# PCB_111000_CC.net
KiCad netlist of a schematic drawn in EAGLE
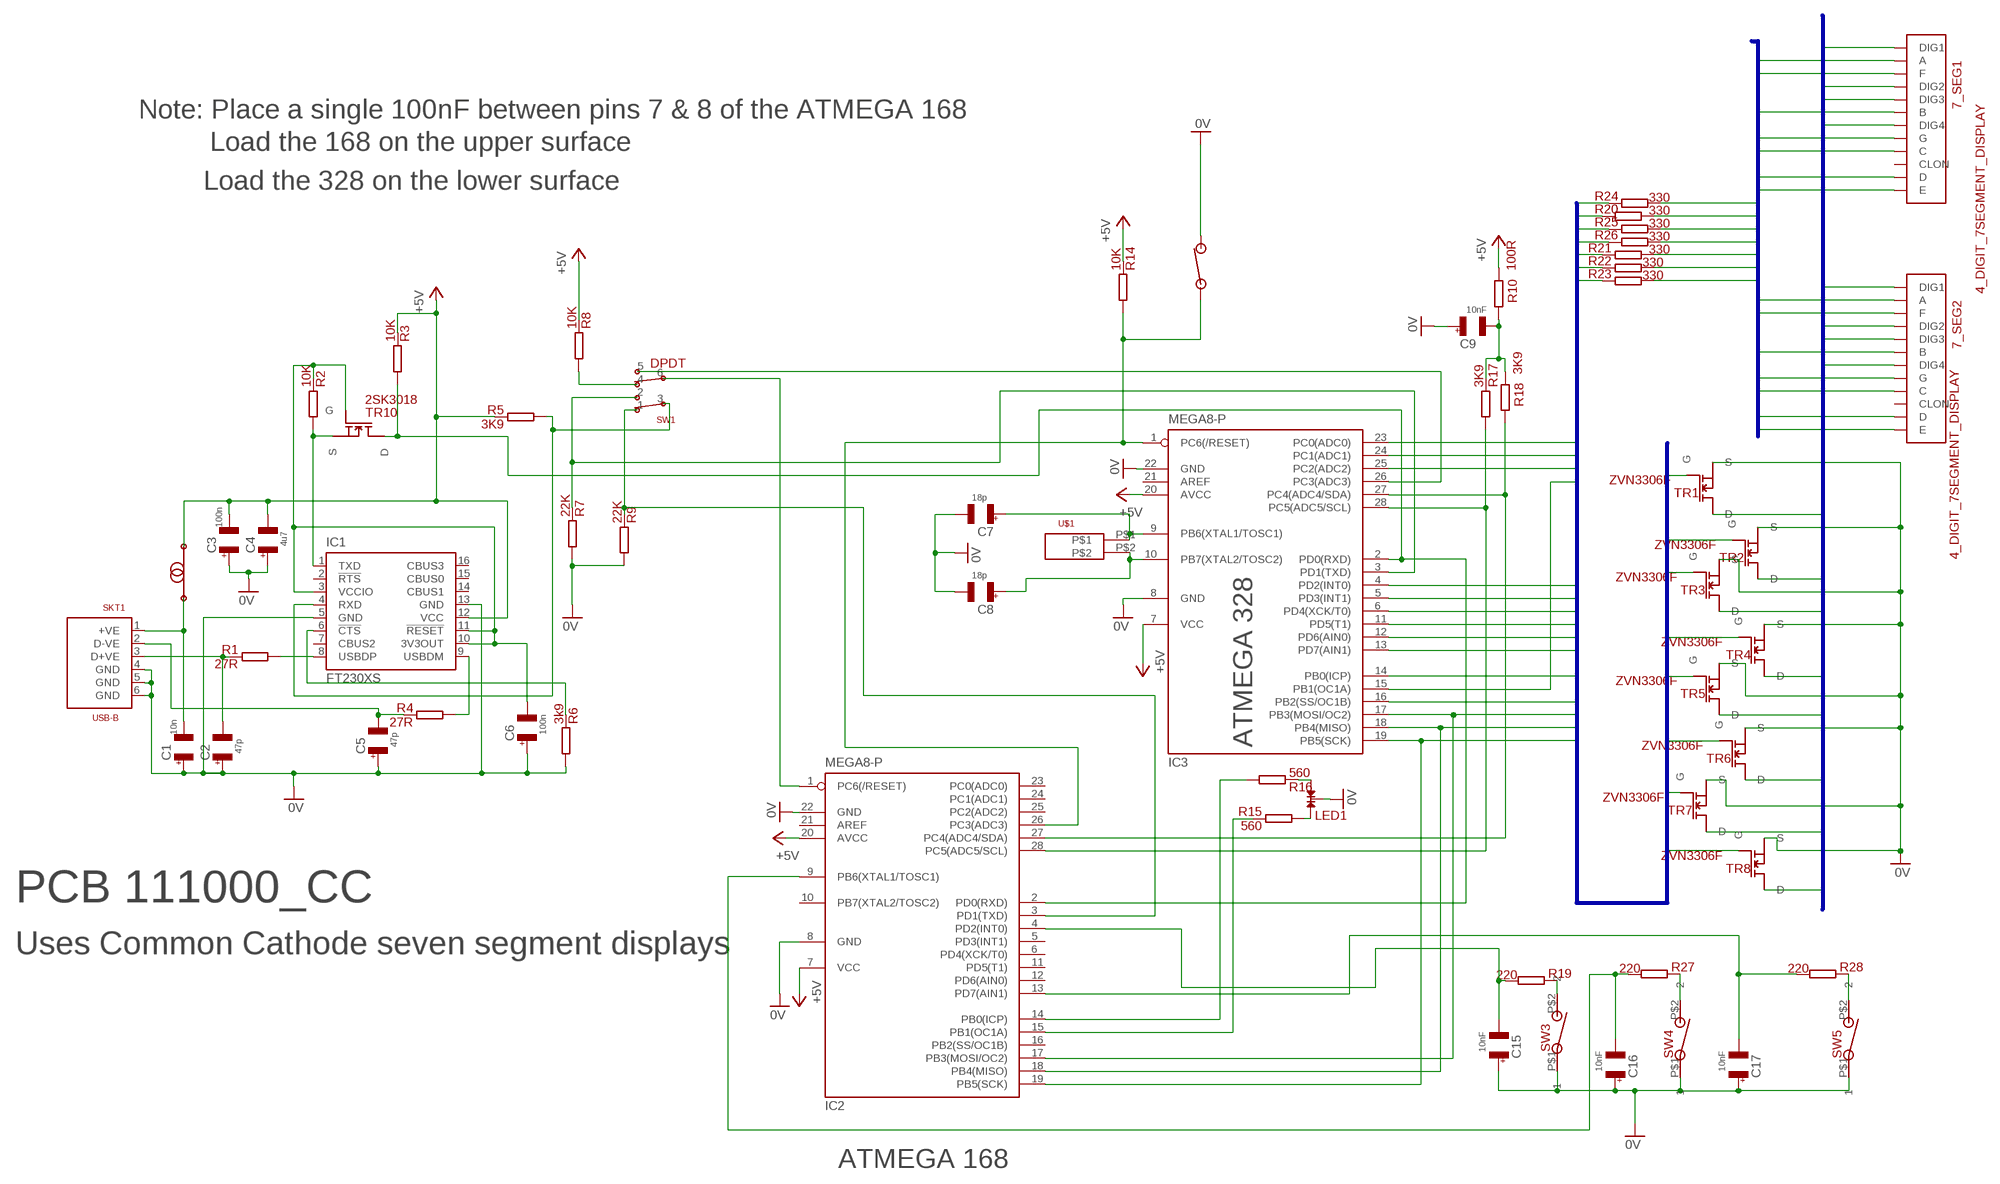
[diagram p0: schematic, sheet 1]

(export (version "E")
  (design (tool "Eeschema 10.0.6"))
  (components
    (comp (ref "7_SEG1")
      (value "4_DIGIT_7SEGMENT_DISPLAY")
      (footprint "eagle-import:4_DIGIT_7SEGMENT_DISPLAY")
      (libsource (lib "eagle-import") (part "4_DIGIT_7SEGMENT_DISPLAY"))
    )
    (comp (ref "7_SEG2")
      (value "4_DIGIT_7SEGMENT_DISPLAY")
      (footprint "eagle-import:4_DIGIT_7SEGMENT_DISPLAY")
      (libsource (lib "eagle-import") (part "4_DIGIT_7SEGMENT_DISPLAY"))
    )
    (comp (ref "C1")
      (value "10n")
      (footprint "eagle-import:1206")
      (libsource (lib "eagle-import") (part "1206C"))
    )
    (comp (ref "C2")
      (value "47p")
      (footprint "eagle-import:1206")
      (libsource (lib "eagle-import") (part "1206C"))
    )
    (comp (ref "C3")
      (value "100n")
      (footprint "eagle-import:1206")
      (libsource (lib "eagle-import") (part "1206C"))
    )
    (comp (ref "C4")
      (value "4u7")
      (footprint "eagle-import:1206")
      (libsource (lib "eagle-import") (part "1206C"))
    )
    (comp (ref "C5")
      (value "47p")
      (footprint "eagle-import:1206")
      (libsource (lib "eagle-import") (part "1206C"))
    )
    (comp (ref "C6")
      (value "100n")
      (footprint "eagle-import:1206")
      (libsource (lib "eagle-import") (part "1206C"))
    )
    (comp (ref "C7")
      (value "18p")
      (footprint "eagle-import:0805")
      (libsource (lib "eagle-import") (part "0805C"))
    )
    (comp (ref "C8")
      (value "18p")
      (footprint "eagle-import:0805")
      (libsource (lib "eagle-import") (part "0805C"))
    )
    (comp (ref "C9")
      (value "10nF")
      (footprint "eagle-import:1206")
      (libsource (lib "eagle-import") (part "1206C"))
    )
    (comp (ref "C15")
      (value "10nF")
      (footprint "eagle-import:1206")
      (libsource (lib "eagle-import") (part "1206C"))
    )
    (comp (ref "C16")
      (value "10nF")
      (footprint "eagle-import:1206")
      (libsource (lib "eagle-import") (part "1206C"))
    )
    (comp (ref "C17")
      (value "10nF")
      (footprint "eagle-import:1206")
      (libsource (lib "eagle-import") (part "1206C"))
    )
    (comp (ref "IC1")
      (value "FT230XS")
      (footprint "eagle-import:SSOP16")
      (libsource (lib "eagle-import") (part "FT230XS"))
    )
    (comp (ref "IC2")
      (value "MEGA8-P")
      (footprint "eagle-import:DIL28-3")
      (libsource (lib "eagle-import") (part "MEGA8-P"))
    )
    (comp (ref "IC3")
      (value "MEGA8-P")
      (footprint "eagle-import:DIL28-3")
      (libsource (lib "eagle-import") (part "MEGA8-P"))
    )
    (comp (ref "L1")
      (value "CHOKE")
      (footprint "eagle-import:1206")
      (libsource (lib "eagle-import") (part "CHOKE"))
    )
    (comp (ref "LED1")
      (value "LED")
      (footprint "eagle-import:CA_DUAL_LED")
      (libsource (lib "eagle-import") (part "LED"))
    )
    (comp (ref "R1")
      (value "27R")
      (footprint "eagle-import:1206")
      (libsource (lib "eagle-import") (part "1206R"))
    )
    (comp (ref "R2")
      (value "10K")
      (footprint "eagle-import:1206")
      (libsource (lib "eagle-import") (part "1206R"))
    )
    (comp (ref "R3")
      (value "10K")
      (footprint "eagle-import:1206")
      (libsource (lib "eagle-import") (part "1206R"))
    )
    (comp (ref "R4")
      (value "27R")
      (footprint "eagle-import:1206")
      (libsource (lib "eagle-import") (part "1206R"))
    )
    (comp (ref "R5")
      (value "3K9")
      (footprint "eagle-import:1206")
      (libsource (lib "eagle-import") (part "1206R"))
    )
    (comp (ref "R6")
      (value "3k9")
      (footprint "eagle-import:1206")
      (libsource (lib "eagle-import") (part "1206R"))
    )
    (comp (ref "R7")
      (value "22K")
      (footprint "eagle-import:1206")
      (libsource (lib "eagle-import") (part "1206R"))
    )
    (comp (ref "R8")
      (value "10K")
      (footprint "eagle-import:1206")
      (libsource (lib "eagle-import") (part "1206R"))
    )
    (comp (ref "R9")
      (value "22K")
      (footprint "eagle-import:1206")
      (libsource (lib "eagle-import") (part "1206R"))
    )
    (comp (ref "R10")
      (value "100R")
      (footprint "eagle-import:1206")
      (libsource (lib "eagle-import") (part "1206R"))
    )
    (comp (ref "R14")
      (value "10K")
      (footprint "eagle-import:1206")
      (libsource (lib "eagle-import") (part "1206R"))
    )
    (comp (ref "R15")
      (value "560")
      (footprint "eagle-import:1206")
      (libsource (lib "eagle-import") (part "1206R"))
    )
    (comp (ref "R16")
      (value "560")
      (footprint "eagle-import:1206")
      (libsource (lib "eagle-import") (part "1206R"))
    )
    (comp (ref "R17")
      (value "3K9")
      (footprint "eagle-import:1206")
      (libsource (lib "eagle-import") (part "1206R"))
    )
    (comp (ref "R18")
      (value "3K9")
      (footprint "eagle-import:1206")
      (libsource (lib "eagle-import") (part "1206R"))
    )
    (comp (ref "R19")
      (value "220")
      (footprint "eagle-import:1206")
      (libsource (lib "eagle-import") (part "1206R"))
    )
    (comp (ref "R20")
      (value "330")
      (footprint "eagle-import:1206")
      (libsource (lib "eagle-import") (part "1206R"))
    )
    (comp (ref "R21")
      (value "330")
      (footprint "eagle-import:1206")
      (libsource (lib "eagle-import") (part "1206R"))
    )
    (comp (ref "R22")
      (value "330")
      (footprint "eagle-import:1206")
      (libsource (lib "eagle-import") (part "1206R"))
    )
    (comp (ref "R23")
      (value "330")
      (footprint "eagle-import:1206")
      (libsource (lib "eagle-import") (part "1206R"))
    )
    (comp (ref "R24")
      (value "330")
      (footprint "eagle-import:1206")
      (libsource (lib "eagle-import") (part "1206R"))
    )
    (comp (ref "R25")
      (value "330")
      (footprint "eagle-import:1206")
      (libsource (lib "eagle-import") (part "1206R"))
    )
    (comp (ref "R26")
      (value "330")
      (footprint "eagle-import:1206")
      (libsource (lib "eagle-import") (part "1206R"))
    )
    (comp (ref "R27")
      (value "220")
      (footprint "eagle-import:1206")
      (libsource (lib "eagle-import") (part "1206R"))
    )
    (comp (ref "R28")
      (value "220")
      (footprint "eagle-import:1206")
      (libsource (lib "eagle-import") (part "1206R"))
    )
    (comp (ref "SKT1")
      (value "USB-B")
      (footprint "eagle-import:USB-B")
      (libsource (lib "eagle-import") (part "USB-B"))
    )
    (comp (ref "SW1")
      (value "DPDT")
      (footprint "eagle-import:DPDT_SWITCH")
      (libsource (lib "eagle-import") (part "DPDT"))
    )
    (comp (ref "SW2")
      (value "NO_SW")
      (footprint "eagle-import:SM_NO_PUSH_BUTTON")
      (libsource (lib "eagle-import") (part "NO_SW"))
    )
    (comp (ref "SW3")
      (value "NO_PB_1")
      (footprint "eagle-import:RE51-0711")
      (libsource (lib "eagle-import") (part "NO_PB_1"))
    )
    (comp (ref "SW4")
      (value "NO_PB_1")
      (footprint "eagle-import:RE51-0711")
      (libsource (lib "eagle-import") (part "NO_PB_1"))
    )
    (comp (ref "SW5")
      (value "NO_PB_1")
      (footprint "eagle-import:RE51-0711")
      (libsource (lib "eagle-import") (part "NO_PB_1"))
    )
    (comp (ref "TR1")
      (value "ZVN3306F")
      (footprint "eagle-import:SOT23")
      (libsource (lib "eagle-import") (part "ZVN3306F"))
    )
    (comp (ref "TR2")
      (value "ZVN3306F")
      (footprint "eagle-import:SOT23")
      (libsource (lib "eagle-import") (part "ZVN3306F"))
    )
    (comp (ref "TR3")
      (value "ZVN3306F")
      (footprint "eagle-import:SOT23")
      (libsource (lib "eagle-import") (part "ZVN3306F"))
    )
    (comp (ref "TR4")
      (value "ZVN3306F")
      (footprint "eagle-import:SOT23")
      (libsource (lib "eagle-import") (part "ZVN3306F"))
    )
    (comp (ref "TR5")
      (value "ZVN3306F")
      (footprint "eagle-import:SOT23")
      (libsource (lib "eagle-import") (part "ZVN3306F"))
    )
    (comp (ref "TR6")
      (value "ZVN3306F")
      (footprint "eagle-import:SOT23")
      (libsource (lib "eagle-import") (part "ZVN3306F"))
    )
    (comp (ref "TR7")
      (value "ZVN3306F")
      (footprint "eagle-import:SOT23")
      (libsource (lib "eagle-import") (part "ZVN3306F"))
    )
    (comp (ref "TR8")
      (value "ZVN3306F")
      (footprint "eagle-import:SOT23")
      (libsource (lib "eagle-import") (part "ZVN3306F"))
    )
    (comp (ref "TR10")
      (value "2SK3018")
      (footprint "eagle-import:2SK3018")
      (libsource (lib "eagle-import") (part "2SK3018"))
    )
    (comp (ref "U$1")
      (value "XTAL")
      (footprint "eagle-import:XTAL_VIAS")
      (libsource (lib "eagle-import") (part "XTAL"))
    )
  )
  (nets
    (net (code "1") (name "+5V") (class "Default")
      (node (ref "C3") (pin "P$2") (pinfunction "2_P$2") (pintype "bidirectional"))
      (node (ref "C4") (pin "P$2") (pinfunction "2_P$2") (pintype "bidirectional"))
      (node (ref "IC1") (pin "12") (pinfunction "VCC_12") (pintype "power_in"))
      (node (ref "IC2") (pin "20") (pinfunction "AVCC_20") (pintype "power_in"))
      (node (ref "IC2") (pin "7") (pinfunction "VCC_7") (pintype "power_in"))
      (node (ref "IC3") (pin "20") (pinfunction "AVCC_20") (pintype "power_in"))
      (node (ref "IC3") (pin "7") (pinfunction "VCC_7") (pintype "power_in"))
      (node (ref "L1") (pin "P$2") (pinfunction "2_P$2") (pintype "bidirectional"))
      (node (ref "R10") (pin "P$2") (pinfunction "P$2_P$2") (pintype "bidirectional"))
      (node (ref "R14") (pin "P$2") (pinfunction "P$2_P$2") (pintype "bidirectional"))
      (node (ref "R3") (pin "P$2") (pinfunction "P$2_P$2") (pintype "bidirectional"))
      (node (ref "R5") (pin "P$2") (pinfunction "P$2_P$2") (pintype "bidirectional"))
      (node (ref "R8") (pin "P$2") (pinfunction "P$2_P$2") (pintype "bidirectional"))
    )
    (net (code "2") (name "/DIGIT0") (class "Default")
      (node (ref "7_SEG1") (pin "P$12") (pinfunction "DIG1_P$12") (pintype "bidirectional"))
      (node (ref "TR5") (pin "3") (pinfunction "D_3") (pintype "bidirectional"))
    )
    (net (code "3") (name "/DIGIT1") (class "Default")
      (node (ref "7_SEG1") (pin "P$9") (pinfunction "DIG2_P$9") (pintype "bidirectional"))
      (node (ref "TR6") (pin "3") (pinfunction "D_3") (pintype "bidirectional"))
    )
    (net (code "4") (name "/DIGIT2") (class "Default")
      (node (ref "7_SEG1") (pin "P$8") (pinfunction "DIG3_P$8") (pintype "bidirectional"))
      (node (ref "TR7") (pin "3") (pinfunction "D_3") (pintype "bidirectional"))
    )
    (net (code "5") (name "/DIGIT3") (class "Default")
      (node (ref "7_SEG1") (pin "P$6") (pinfunction "DIG4_P$6") (pintype "bidirectional"))
      (node (ref "TR8") (pin "3") (pinfunction "D_3") (pintype "bidirectional"))
    )
    (net (code "6") (name "/DIGIT4") (class "Default")
      (node (ref "7_SEG2") (pin "P$12") (pinfunction "DIG1_P$12") (pintype "bidirectional"))
      (node (ref "TR1") (pin "3") (pinfunction "D_3") (pintype "bidirectional"))
    )
    (net (code "7") (name "/DIGIT5") (class "Default")
      (node (ref "7_SEG2") (pin "P$9") (pinfunction "DIG2_P$9") (pintype "bidirectional"))
      (node (ref "TR2") (pin "3") (pinfunction "D_3") (pintype "bidirectional"))
    )
    (net (code "8") (name "/DIGIT6") (class "Default")
      (node (ref "7_SEG2") (pin "P$8") (pinfunction "DIG3_P$8") (pintype "bidirectional"))
      (node (ref "TR3") (pin "3") (pinfunction "D_3") (pintype "bidirectional"))
    )
    (net (code "9") (name "/DIGIT7") (class "Default")
      (node (ref "7_SEG2") (pin "P$6") (pinfunction "DIG4_P$6") (pintype "bidirectional"))
      (node (ref "TR4") (pin "3") (pinfunction "D_3") (pintype "bidirectional"))
    )
    (net (code "10") (name "/DISPLAY_DRIVER0") (class "Default")
      (node (ref "IC3") (pin "15") (pinfunction "PB1(OC1A)_15") (pintype "bidirectional"))
      (node (ref "R24") (pin "P$2") (pinfunction "P$2_P$2") (pintype "bidirectional"))
    )
    (net (code "11") (name "/DISPLAY_DRIVER1") (class "Default")
      (node (ref "IC3") (pin "4") (pinfunction "PD2(INT0)_4") (pintype "bidirectional"))
      (node (ref "R20") (pin "P$2") (pinfunction "P$2_P$2") (pintype "bidirectional"))
    )
    (net (code "12") (name "/DISPLAY_DRIVER2") (class "Default")
      (node (ref "IC3") (pin "5") (pinfunction "PD3(INT1)_5") (pintype "bidirectional"))
      (node (ref "R25") (pin "P$2") (pinfunction "P$2_P$2") (pintype "bidirectional"))
    )
    (net (code "13") (name "/DISPLAY_DRIVER3") (class "Default")
      (node (ref "IC3") (pin "6") (pinfunction "PD4(XCK/T0)_6") (pintype "bidirectional"))
      (node (ref "R26") (pin "P$2") (pinfunction "P$2_P$2") (pintype "bidirectional"))
    )
    (net (code "14") (name "/DISPLAY_DRIVER4") (class "Default")
      (node (ref "IC3") (pin "11") (pinfunction "PD5(T1)_11") (pintype "bidirectional"))
      (node (ref "R21") (pin "P$2") (pinfunction "P$2_P$2") (pintype "bidirectional"))
    )
    (net (code "15") (name "/DISPLAY_DRIVER5") (class "Default")
      (node (ref "IC3") (pin "12") (pinfunction "PD6(AIN0)_12") (pintype "bidirectional"))
      (node (ref "R22") (pin "P$2") (pinfunction "P$2_P$2") (pintype "bidirectional"))
    )
    (net (code "16") (name "/DISPLAY_DRIVER6") (class "Default")
      (node (ref "IC3") (pin "13") (pinfunction "PD7(AIN1)_13") (pintype "bidirectional"))
      (node (ref "R23") (pin "P$2") (pinfunction "P$2_P$2") (pintype "bidirectional"))
    )
    (net (code "17") (name "/DISPLAY_DRIVER8") (class "Default")
      (node (ref "IC3") (pin "14") (pinfunction "PB0(ICP)_14") (pintype "bidirectional"))
      (node (ref "TR1") (pin "1") (pinfunction "G_1") (pintype "bidirectional"))
    )
    (net (code "18") (name "/DISPLAY_DRIVER9") (class "Default")
      (node (ref "IC3") (pin "16") (pinfunction "PB2(SS/OC1B)_16") (pintype "bidirectional"))
      (node (ref "TR2") (pin "1") (pinfunction "G_1") (pintype "bidirectional"))
    )
    (net (code "19") (name "/DISPLAY_DRIVER10") (class "Default")
      (node (ref "IC2") (pin "17") (pinfunction "PB3(MOSI/OC2)_17") (pintype "bidirectional"))
      (node (ref "IC3") (pin "17") (pinfunction "PB3(MOSI/OC2)_17") (pintype "bidirectional"))
      (node (ref "TR3") (pin "1") (pinfunction "G_1") (pintype "bidirectional"))
    )
    (net (code "20") (name "/DISPLAY_DRIVER11") (class "Default")
      (node (ref "IC2") (pin "18") (pinfunction "PB4(MISO)_18") (pintype "bidirectional"))
      (node (ref "IC3") (pin "18") (pinfunction "PB4(MISO)_18") (pintype "bidirectional"))
      (node (ref "TR4") (pin "1") (pinfunction "G_1") (pintype "bidirectional"))
    )
    (net (code "21") (name "/DISPLAY_DRIVER12") (class "Default")
      (node (ref "IC2") (pin "19") (pinfunction "PB5(SCK)_19") (pintype "bidirectional"))
      (node (ref "IC3") (pin "19") (pinfunction "PB5(SCK)_19") (pintype "bidirectional"))
      (node (ref "TR5") (pin "1") (pinfunction "G_1") (pintype "bidirectional"))
    )
    (net (code "22") (name "/DISPLAY_DRIVER13") (class "Default")
      (node (ref "IC3") (pin "23") (pinfunction "PC0(ADC0)_23") (pintype "bidirectional"))
      (node (ref "TR6") (pin "1") (pinfunction "G_1") (pintype "bidirectional"))
    )
    (net (code "23") (name "/DISPLAY_DRIVER14") (class "Default")
      (node (ref "IC3") (pin "24") (pinfunction "PC1(ADC1)_24") (pintype "bidirectional"))
      (node (ref "TR7") (pin "1") (pinfunction "G_1") (pintype "bidirectional"))
    )
    (net (code "24") (name "/DISPLAY_DRIVER15") (class "Default")
      (node (ref "IC3") (pin "25") (pinfunction "PC2(ADC2)_25") (pintype "bidirectional"))
      (node (ref "TR8") (pin "1") (pinfunction "G_1") (pintype "bidirectional"))
    )
    (net (code "25") (name "/SEVEN_SEG0") (class "Default")
      (node (ref "7_SEG1") (pin "P$11") (pinfunction "A_P$11") (pintype "bidirectional"))
      (node (ref "7_SEG2") (pin "P$11") (pinfunction "A_P$11") (pintype "bidirectional"))
      (node (ref "R24") (pin "P$1") (pinfunction "P$1_P$1") (pintype "bidirectional"))
    )
    (net (code "26") (name "/SEVEN_SEG1") (class "Default")
      (node (ref "7_SEG1") (pin "P$7") (pinfunction "B_P$7") (pintype "bidirectional"))
      (node (ref "7_SEG2") (pin "P$7") (pinfunction "B_P$7") (pintype "bidirectional"))
      (node (ref "R20") (pin "P$1") (pinfunction "P$1_P$1") (pintype "bidirectional"))
    )
    (net (code "27") (name "/SEVEN_SEG2") (class "Default")
      (node (ref "7_SEG1") (pin "P$4") (pinfunction "C_P$4") (pintype "bidirectional"))
      (node (ref "7_SEG2") (pin "P$4") (pinfunction "C_P$4") (pintype "bidirectional"))
      (node (ref "R25") (pin "P$1") (pinfunction "P$1_P$1") (pintype "bidirectional"))
    )
    (net (code "28") (name "/SEVEN_SEG3") (class "Default")
      (node (ref "7_SEG1") (pin "P$2") (pinfunction "D_P$2") (pintype "bidirectional"))
      (node (ref "7_SEG2") (pin "P$2") (pinfunction "D_P$2") (pintype "bidirectional"))
      (node (ref "R26") (pin "P$1") (pinfunction "P$1_P$1") (pintype "bidirectional"))
    )
    (net (code "29") (name "/SEVEN_SEG4") (class "Default")
      (node (ref "7_SEG1") (pin "P$1") (pinfunction "E_P$1") (pintype "bidirectional"))
      (node (ref "7_SEG2") (pin "P$1") (pinfunction "E_P$1") (pintype "bidirectional"))
      (node (ref "R21") (pin "P$1") (pinfunction "P$1_P$1") (pintype "bidirectional"))
    )
    (net (code "30") (name "/SEVEN_SEG5") (class "Default")
      (node (ref "7_SEG1") (pin "P$10") (pinfunction "F_P$10") (pintype "bidirectional"))
      (node (ref "7_SEG2") (pin "P$10") (pinfunction "F_P$10") (pintype "bidirectional"))
      (node (ref "R22") (pin "P$1") (pinfunction "P$1_P$1") (pintype "bidirectional"))
    )
    (net (code "31") (name "/SEVEN_SEG6") (class "Default")
      (node (ref "7_SEG1") (pin "P$5") (pinfunction "G_P$5") (pintype "bidirectional"))
      (node (ref "7_SEG2") (pin "P$5") (pinfunction "G_P$5") (pintype "bidirectional"))
      (node (ref "R23") (pin "P$1") (pinfunction "P$1_P$1") (pintype "bidirectional"))
    )
    (net (code "32") (name "0V") (class "Default")
      (node (ref "C1") (pin "P$1") (pinfunction "1_P$1") (pintype "bidirectional"))
      (node (ref "C15") (pin "P$1") (pinfunction "1_P$1") (pintype "bidirectional"))
      (node (ref "C16") (pin "P$1") (pinfunction "1_P$1") (pintype "bidirectional"))
      (node (ref "C17") (pin "P$1") (pinfunction "1_P$1") (pintype "bidirectional"))
      (node (ref "C2") (pin "P$1") (pinfunction "1_P$1") (pintype "bidirectional"))
      (node (ref "C3") (pin "P$1") (pinfunction "1_P$1") (pintype "bidirectional"))
      (node (ref "C4") (pin "P$1") (pinfunction "1_P$1") (pintype "bidirectional"))
      (node (ref "C5") (pin "P$1") (pinfunction "1_P$1") (pintype "bidirectional"))
      (node (ref "C6") (pin "P$1") (pinfunction "1_P$1") (pintype "bidirectional"))
      (node (ref "C7") (pin "2") (pinfunction "2_2") (pintype "bidirectional"))
      (node (ref "C8") (pin "2") (pinfunction "2_2") (pintype "bidirectional"))
      (node (ref "C9") (pin "P$1") (pinfunction "1_P$1") (pintype "bidirectional"))
      (node (ref "IC1") (pin "13") (pinfunction "GND_13") (pintype "power_in"))
      (node (ref "IC1") (pin "5") (pinfunction "GND_5") (pintype "power_in"))
      (node (ref "IC2") (pin "22") (pinfunction "GND_22") (pintype "power_in"))
      (node (ref "IC2") (pin "8") (pinfunction "GND_8") (pintype "power_in"))
      (node (ref "IC3") (pin "22") (pinfunction "GND_22") (pintype "power_in"))
      (node (ref "IC3") (pin "8") (pinfunction "GND_8") (pintype "power_in"))
      (node (ref "LED1") (pin "2") (pinfunction "2_2") (pintype "bidirectional"))
      (node (ref "R6") (pin "P$1") (pinfunction "P$1_P$1") (pintype "bidirectional"))
      (node (ref "R7") (pin "P$1") (pinfunction "P$1_P$1") (pintype "bidirectional"))
      (node (ref "R9") (pin "P$1") (pinfunction "P$1_P$1") (pintype "bidirectional"))
      (node (ref "SKT1") (pin "4") (pinfunction "GND_4") (pintype "bidirectional"))
      (node (ref "SKT1") (pin "5") (pinfunction "GND_5") (pintype "bidirectional"))
      (node (ref "SKT1") (pin "6") (pinfunction "GND_6") (pintype "bidirectional"))
      (node (ref "SW2") (pin "P$2") (pinfunction "2_P$2") (pintype "bidirectional"))
      (node (ref "SW3") (pin "P$1") (pinfunction "1_P$1") (pintype "bidirectional"))
      (node (ref "SW4") (pin "P$1") (pinfunction "1_P$1") (pintype "bidirectional"))
      (node (ref "SW5") (pin "P$1") (pinfunction "1_P$1") (pintype "bidirectional"))
      (node (ref "TR1") (pin "2") (pinfunction "S_2") (pintype "bidirectional"))
      (node (ref "TR2") (pin "2") (pinfunction "S_2") (pintype "bidirectional"))
      (node (ref "TR3") (pin "2") (pinfunction "S_2") (pintype "bidirectional"))
      (node (ref "TR4") (pin "2") (pinfunction "S_2") (pintype "bidirectional"))
      (node (ref "TR5") (pin "2") (pinfunction "S_2") (pintype "bidirectional"))
      (node (ref "TR6") (pin "2") (pinfunction "S_2") (pintype "bidirectional"))
      (node (ref "TR7") (pin "2") (pinfunction "S_2") (pintype "bidirectional"))
      (node (ref "TR8") (pin "2") (pinfunction "S_2") (pintype "bidirectional"))
    )
    (net (code "33") (name "Net-(C1-2)") (class "Default")
      (node (ref "C1") (pin "P$2") (pinfunction "2_P$2") (pintype "bidirectional"))
      (node (ref "L1") (pin "P$1") (pinfunction "1_P$1") (pintype "bidirectional"))
      (node (ref "SKT1") (pin "1") (pinfunction "+VE_1") (pintype "bidirectional"))
    )
    (net (code "34") (name "Net-(C2-2)") (class "Default")
      (node (ref "C2") (pin "P$2") (pinfunction "2_P$2") (pintype "bidirectional"))
      (node (ref "R1") (pin "P$2") (pinfunction "P$2_P$2") (pintype "bidirectional"))
      (node (ref "SKT1") (pin "3") (pinfunction "D+VE_3") (pintype "bidirectional"))
    )
    (net (code "35") (name "Net-(C5-2)") (class "Default")
      (node (ref "C5") (pin "P$2") (pinfunction "2_P$2") (pintype "bidirectional"))
      (node (ref "R4") (pin "P$2") (pinfunction "P$2_P$2") (pintype "bidirectional"))
      (node (ref "SKT1") (pin "2") (pinfunction "D-VE_2") (pintype "bidirectional"))
    )
    (net (code "36") (name "Net-(C6-2)") (class "Default")
      (node (ref "C6") (pin "P$2") (pinfunction "2_P$2") (pintype "bidirectional"))
      (node (ref "IC1") (pin "10") (pinfunction "3V3OUT_10") (pintype "output"))
      (node (ref "IC1") (pin "11") (pinfunction "~{RESET}_11") (pintype "input"))
      (node (ref "IC1") (pin "3") (pinfunction "VCCIO_3") (pintype "power_in"))
      (node (ref "R2") (pin "P$2") (pinfunction "P$2_P$2") (pintype "bidirectional"))
      (node (ref "TR10") (pin "2") (pinfunction "G_2") (pintype "bidirectional"))
    )
    (net (code "37") (name "Net-(C9-2)") (class "Default")
      (node (ref "C9") (pin "P$2") (pinfunction "2_P$2") (pintype "bidirectional"))
      (node (ref "R10") (pin "P$1") (pinfunction "P$1_P$1") (pintype "bidirectional"))
      (node (ref "R17") (pin "P$2") (pinfunction "P$2_P$2") (pintype "bidirectional"))
      (node (ref "R18") (pin "P$2") (pinfunction "P$2_P$2") (pintype "bidirectional"))
    )
    (net (code "38") (name "Net-(C15-2)") (class "Default")
      (node (ref "C15") (pin "P$2") (pinfunction "2_P$2") (pintype "bidirectional"))
      (node (ref "IC2") (pin "4") (pinfunction "PD2(INT0)_4") (pintype "bidirectional"))
      (node (ref "R19") (pin "P$1") (pinfunction "P$1_P$1") (pintype "bidirectional"))
    )
    (net (code "39") (name "Net-(C16-2)") (class "Default")
      (node (ref "C16") (pin "P$2") (pinfunction "2_P$2") (pintype "bidirectional"))
      (node (ref "IC2") (pin "9") (pinfunction "PB6(XTAL1/TOSC1)_9") (pintype "bidirectional"))
      (node (ref "R27") (pin "P$1") (pinfunction "P$1_P$1") (pintype "bidirectional"))
    )
    (net (code "40") (name "Net-(C17-2)") (class "Default")
      (node (ref "C17") (pin "P$2") (pinfunction "2_P$2") (pintype "bidirectional"))
      (node (ref "IC2") (pin "13") (pinfunction "PD7(AIN1)_13") (pintype "bidirectional"))
      (node (ref "R28") (pin "P$1") (pinfunction "P$1_P$1") (pintype "bidirectional"))
    )
    (net (code "41") (name "Net-(IC1-RXD)") (class "Default")
      (node (ref "IC1") (pin "4") (pinfunction "RXD_4") (pintype "input"))
      (node (ref "R5") (pin "P$1") (pinfunction "P$1_P$1") (pintype "bidirectional"))
      (node (ref "SW1") (pin "3") (pinfunction "3_3") (pintype "bidirectional"))
    )
    (net (code "42") (name "Net-(IC1-TXD)") (class "Default")
      (node (ref "IC1") (pin "1") (pinfunction "TXD_1") (pintype "output"))
      (node (ref "R2") (pin "P$1") (pinfunction "P$1_P$1") (pintype "bidirectional"))
      (node (ref "TR10") (pin "1") (pinfunction "S_1") (pintype "bidirectional"))
    )
    (net (code "43") (name "Net-(IC1-USBDM)") (class "Default")
      (node (ref "IC1") (pin "9") (pinfunction "USBDM_9") (pintype "input"))
      (node (ref "R4") (pin "P$1") (pinfunction "P$1_P$1") (pintype "bidirectional"))
    )
    (net (code "44") (name "Net-(IC1-USBDP)") (class "Default")
      (node (ref "IC1") (pin "8") (pinfunction "USBDP_8") (pintype "input"))
      (node (ref "R1") (pin "P$1") (pinfunction "P$1_P$1") (pintype "bidirectional"))
    )
    (net (code "45") (name "Net-(IC1-~{CTS})") (class "Default")
      (node (ref "IC1") (pin "6") (pinfunction "~{CTS}_6") (pintype "input"))
      (node (ref "R6") (pin "P$2") (pinfunction "P$2_P$2") (pintype "bidirectional"))
    )
    (net (code "46") (name "Net-(IC2-PB0(ICP))") (class "Default")
      (node (ref "IC2") (pin "14") (pinfunction "PB0(ICP)_14") (pintype "bidirectional"))
      (node (ref "R16") (pin "P$1") (pinfunction "P$1_P$1") (pintype "bidirectional"))
    )
    (net (code "47") (name "Net-(IC2-PB1(OC1A))") (class "Default")
      (node (ref "IC2") (pin "15") (pinfunction "PB1(OC1A)_15") (pintype "bidirectional"))
      (node (ref "R15") (pin "P$2") (pinfunction "P$2_P$2") (pintype "bidirectional"))
    )
    (net (code "48") (name "Net-(IC2-PC3(ADC3))") (class "Default")
      (node (ref "IC2") (pin "26") (pinfunction "PC3(ADC3)_26") (pintype "bidirectional"))
      (node (ref "IC3") (pin "1") (pinfunction "PC6(/RESET)_1") (pintype "bidirectional"))
      (node (ref "R14") (pin "P$1") (pinfunction "P$1_P$1") (pintype "bidirectional"))
      (node (ref "SW2") (pin "P$1") (pinfunction "1_P$1") (pintype "bidirectional"))
    )
    (net (code "49") (name "Net-(IC2-PC4(ADC4{slash}SDA))") (class "Default")
      (node (ref "IC2") (pin "27") (pinfunction "PC4(ADC4/SDA)_27") (pintype "bidirectional"))
      (node (ref "IC3") (pin "27") (pinfunction "PC4(ADC4/SDA)_27") (pintype "bidirectional"))
      (node (ref "R18") (pin "P$1") (pinfunction "P$1_P$1") (pintype "bidirectional"))
    )
    (net (code "50") (name "Net-(IC2-PC5(ADC5{slash}SCL))") (class "Default")
      (node (ref "IC2") (pin "28") (pinfunction "PC5(ADC5/SCL)_28") (pintype "bidirectional"))
      (node (ref "IC3") (pin "28") (pinfunction "PC5(ADC5/SCL)_28") (pintype "bidirectional"))
      (node (ref "R17") (pin "P$1") (pinfunction "P$1_P$1") (pintype "bidirectional"))
    )
    (net (code "51") (name "Net-(IC2-PC6({slash}RESET))") (class "Default")
      (node (ref "IC2") (pin "1") (pinfunction "PC6(/RESET)_1") (pintype "bidirectional"))
      (node (ref "SW1") (pin "6") (pinfunction "6_6") (pintype "bidirectional"))
    )
    (net (code "52") (name "Net-(IC2-PD0(RXD))") (class "Default")
      (node (ref "IC2") (pin "2") (pinfunction "PD0(RXD)_2") (pintype "bidirectional"))
      (node (ref "IC3") (pin "2") (pinfunction "PD0(RXD)_2") (pintype "bidirectional"))
      (node (ref "R3") (pin "P$1") (pinfunction "P$1_P$1") (pintype "bidirectional"))
      (node (ref "TR10") (pin "3") (pinfunction "D_3") (pintype "bidirectional"))
    )
    (net (code "53") (name "Net-(IC2-PD1(TXD))") (class "Default")
      (node (ref "IC2") (pin "3") (pinfunction "PD1(TXD)_3") (pintype "bidirectional"))
      (node (ref "R9") (pin "P$2") (pinfunction "P$2_P$2") (pintype "bidirectional"))
      (node (ref "SW1") (pin "1") (pinfunction "1_1") (pintype "bidirectional"))
    )
    (net (code "54") (name "Net-(IC3-PB6(XTAL1{slash}TOSC1))") (class "Default")
      (node (ref "C7") (pin "1") (pinfunction "1_1") (pintype "bidirectional"))
      (node (ref "IC3") (pin "9") (pinfunction "PB6(XTAL1/TOSC1)_9") (pintype "bidirectional"))
      (node (ref "U$1") (pin "P$1") (pinfunction "P$1_P$1") (pintype "bidirectional"))
    )
    (net (code "55") (name "Net-(IC3-PB7(XTAL2{slash}TOSC2))") (class "Default")
      (node (ref "C8") (pin "1") (pinfunction "1_1") (pintype "bidirectional"))
      (node (ref "IC3") (pin "10") (pinfunction "PB7(XTAL2/TOSC2)_10") (pintype "bidirectional"))
      (node (ref "U$1") (pin "P$2") (pinfunction "P$2_P$2") (pintype "bidirectional"))
    )
    (net (code "56") (name "Net-(IC3-PC3(ADC3))") (class "Default")
      (node (ref "IC3") (pin "26") (pinfunction "PC3(ADC3)_26") (pintype "bidirectional"))
      (node (ref "SW1") (pin "5") (pinfunction "5_5") (pintype "bidirectional"))
    )
    (net (code "57") (name "Net-(IC3-PD1(TXD))") (class "Default")
      (node (ref "IC3") (pin "3") (pinfunction "PD1(TXD)_3") (pintype "bidirectional"))
      (node (ref "R7") (pin "P$2") (pinfunction "P$2_P$2") (pintype "bidirectional"))
      (node (ref "SW1") (pin "2") (pinfunction "2_2") (pintype "bidirectional"))
    )
    (net (code "58") (name "Net-(LED1-Pad1)") (class "Default")
      (node (ref "LED1") (pin "1") (pinfunction "1_1") (pintype "bidirectional"))
      (node (ref "R15") (pin "P$1") (pinfunction "P$1_P$1") (pintype "bidirectional"))
    )
    (net (code "59") (name "Net-(LED1-Pad3)") (class "Default")
      (node (ref "LED1") (pin "3") (pinfunction "3_3") (pintype "bidirectional"))
      (node (ref "R16") (pin "P$2") (pinfunction "P$2_P$2") (pintype "bidirectional"))
    )
    (net (code "60") (name "Net-(R8-PadP$1)") (class "Default")
      (node (ref "R8") (pin "P$1") (pinfunction "P$1_P$1") (pintype "bidirectional"))
      (node (ref "SW1") (pin "4") (pinfunction "4_4") (pintype "bidirectional"))
    )
    (net (code "61") (name "Net-(SW3-2)") (class "Default")
      (node (ref "R19") (pin "P$2") (pinfunction "P$2_P$2") (pintype "bidirectional"))
      (node (ref "SW3") (pin "P$2") (pinfunction "2_P$2") (pintype "bidirectional"))
    )
    (net (code "62") (name "Net-(SW4-2)") (class "Default")
      (node (ref "R27") (pin "P$2") (pinfunction "P$2_P$2") (pintype "bidirectional"))
      (node (ref "SW4") (pin "P$2") (pinfunction "2_P$2") (pintype "bidirectional"))
    )
    (net (code "63") (name "Net-(SW5-2)") (class "Default")
      (node (ref "R28") (pin "P$2") (pinfunction "P$2_P$2") (pintype "bidirectional"))
      (node (ref "SW5") (pin "P$2") (pinfunction "2_P$2") (pintype "bidirectional"))
    )
    (net (code "64") (name "unconnected-(7_SEG1-CLON-PadP$3)") (class "Default")
      (node (ref "7_SEG1") (pin "P$3") (pinfunction "CLON_P$3") (pintype "bidirectional"))
    )
    (net (code "65") (name "unconnected-(7_SEG2-CLON-PadP$3)") (class "Default")
      (node (ref "7_SEG2") (pin "P$3") (pinfunction "CLON_P$3") (pintype "bidirectional"))
    )
    (net (code "66") (name "unconnected-(IC1-CBUS0-Pad15)") (class "Default")
      (node (ref "IC1") (pin "15") (pinfunction "CBUS0_15") (pintype "bidirectional"))
    )
    (net (code "67") (name "unconnected-(IC1-CBUS1-Pad14)") (class "Default")
      (node (ref "IC1") (pin "14") (pinfunction "CBUS1_14") (pintype "bidirectional"))
    )
    (net (code "68") (name "unconnected-(IC1-CBUS2-Pad7)") (class "Default")
      (node (ref "IC1") (pin "7") (pinfunction "CBUS2_7") (pintype "bidirectional"))
    )
    (net (code "69") (name "unconnected-(IC1-CBUS3-Pad16)") (class "Default")
      (node (ref "IC1") (pin "16") (pinfunction "CBUS3_16") (pintype "bidirectional"))
    )
    (net (code "70") (name "unconnected-(IC1-~{RTS}-Pad2)") (class "Default")
      (node (ref "IC1") (pin "2") (pinfunction "~{RTS}_2") (pintype "output"))
    )
    (net (code "71") (name "unconnected-(IC2-AREF-Pad21)") (class "Default")
      (node (ref "IC2") (pin "21") (pinfunction "AREF_21") (pintype "passive"))
    )
    (net (code "72") (name "unconnected-(IC2-PB2(SS{slash}OC1B)-Pad16)") (class "Default")
      (node (ref "IC2") (pin "16") (pinfunction "PB2(SS/OC1B)_16") (pintype "bidirectional"))
    )
    (net (code "73") (name "unconnected-(IC2-PB7(XTAL2{slash}TOSC2)-Pad10)") (class "Default")
      (node (ref "IC2") (pin "10") (pinfunction "PB7(XTAL2/TOSC2)_10") (pintype "bidirectional"))
    )
    (net (code "74") (name "unconnected-(IC2-PC0(ADC0)-Pad23)") (class "Default")
      (node (ref "IC2") (pin "23") (pinfunction "PC0(ADC0)_23") (pintype "bidirectional"))
    )
    (net (code "75") (name "unconnected-(IC2-PC1(ADC1)-Pad24)") (class "Default")
      (node (ref "IC2") (pin "24") (pinfunction "PC1(ADC1)_24") (pintype "bidirectional"))
    )
    (net (code "76") (name "unconnected-(IC2-PC2(ADC2)-Pad25)") (class "Default")
      (node (ref "IC2") (pin "25") (pinfunction "PC2(ADC2)_25") (pintype "bidirectional"))
    )
    (net (code "77") (name "unconnected-(IC2-PD3(INT1)-Pad5)") (class "Default")
      (node (ref "IC2") (pin "5") (pinfunction "PD3(INT1)_5") (pintype "bidirectional"))
    )
    (net (code "78") (name "unconnected-(IC2-PD4(XCK{slash}T0)-Pad6)") (class "Default")
      (node (ref "IC2") (pin "6") (pinfunction "PD4(XCK/T0)_6") (pintype "bidirectional"))
    )
    (net (code "79") (name "unconnected-(IC2-PD5(T1)-Pad11)") (class "Default")
      (node (ref "IC2") (pin "11") (pinfunction "PD5(T1)_11") (pintype "bidirectional"))
    )
    (net (code "80") (name "unconnected-(IC2-PD6(AIN0)-Pad12)") (class "Default")
      (node (ref "IC2") (pin "12") (pinfunction "PD6(AIN0)_12") (pintype "bidirectional"))
    )
    (net (code "81") (name "unconnected-(IC3-AREF-Pad21)") (class "Default")
      (node (ref "IC3") (pin "21") (pinfunction "AREF_21") (pintype "passive"))
    )
  )
)
